# CNC-InterfaceBoard.net
KiCad netlist of a schematic drawn in EAGLE
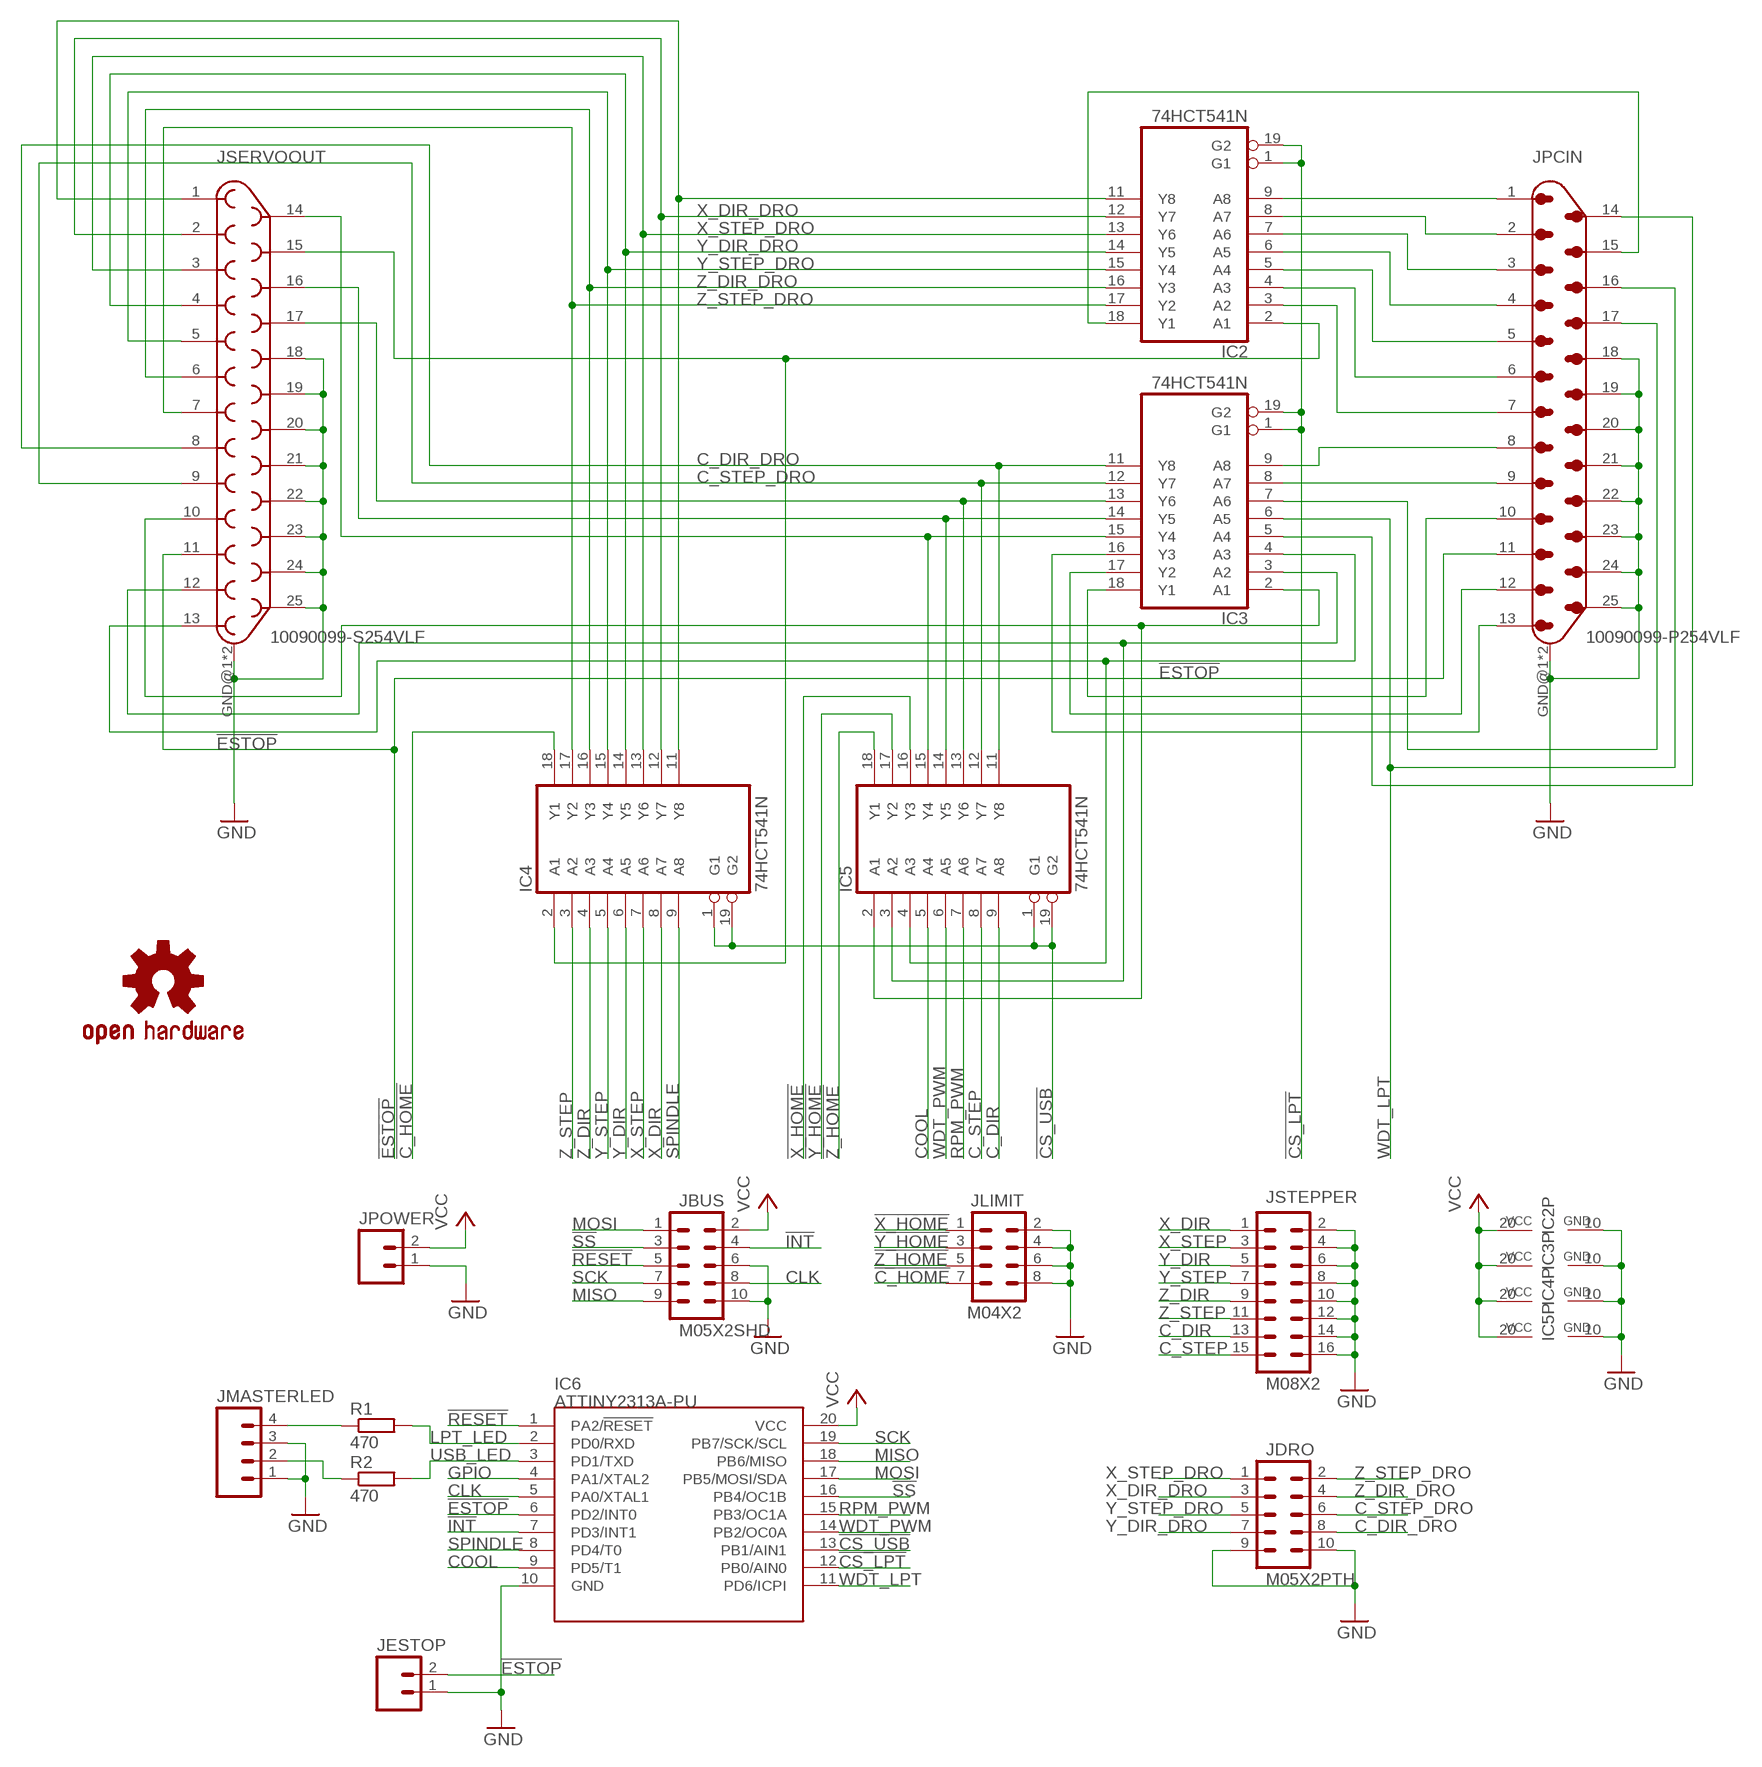
[diagram p0: schematic, sheet 1]

(export (version "E")
  (design (tool "Eeschema 10.0.6"))
  (components
    (comp (ref "IC2")
      (value "74HCT541N")
      (footprint "eagle-import:DIL20")
      (libsource (lib "eagle-import") (part "74541NHCT"))
    )
    (comp (ref "IC3")
      (value "74HCT541N")
      (footprint "eagle-import:DIL20")
      (libsource (lib "eagle-import") (part "74541NHCT"))
    )
    (comp (ref "IC4")
      (value "74HCT541N")
      (footprint "eagle-import:DIL20")
      (libsource (lib "eagle-import") (part "74541NHCT"))
    )
    (comp (ref "IC5")
      (value "74HCT541N")
      (footprint "eagle-import:DIL20")
      (libsource (lib "eagle-import") (part "74541NHCT"))
    )
    (comp (ref "IC6")
      (value "ATTINY2313A-PU")
      (footprint "eagle-import:DIP254P762X533-20")
      (libsource (lib "eagle-import") (part "ATTINY2313A-PU"))
    )
    (comp (ref "JBUS")
      (value "M05X2SHD")
      (footprint "eagle-import:2X5-SHROUDED")
      (libsource (lib "eagle-import") (part "M05X2SHD"))
    )
    (comp (ref "JDRO")
      (value "M05X2PTH")
      (footprint "eagle-import:AVR_ICSP")
      (libsource (lib "eagle-import") (part "M05X2PTH"))
    )
    (comp (ref "JESTOP")
      (value "M02PTH")
      (footprint "eagle-import:1X02")
      (libsource (lib "eagle-import") (part "M02PTH"))
    )
    (comp (ref "JLIMIT")
      (value "M04X2")
      (footprint "eagle-import:2X4")
      (libsource (lib "eagle-import") (part "M04X2"))
    )
    (comp (ref "JMASTERLED")
      (value "M04PTH")
      (footprint "eagle-import:1X04")
      (libsource (lib "eagle-import") (part "M04PTH"))
    )
    (comp (ref "JPCIN")
      (value "10090099-P254VLF")
      (footprint "eagle-import:10090099-P254VLF")
      (libsource (lib "eagle-import") (part "10090099-P254VLF"))
    )
    (comp (ref "JPOWER")
      (value "M02POLAR")
      (footprint "eagle-import:MOLEX-1X2")
      (libsource (lib "eagle-import") (part "M02POLAR"))
    )
    (comp (ref "JSERVOOUT")
      (value "10090099-S254VLF")
      (footprint "eagle-import:10090099-S254VLF")
      (libsource (lib "eagle-import") (part "10090099-S254VLF"))
    )
    (comp (ref "JSTEPPER")
      (value "M08X2")
      (footprint "eagle-import:2X8")
      (libsource (lib "eagle-import") (part "M08X2"))
    )
    (comp (ref "R1")
      (value "470")
      (footprint "eagle-import:0207_10")
      (libsource (lib "eagle-import") (part "R-EU_0207/10"))
    )
    (comp (ref "R2")
      (value "470")
      (footprint "eagle-import:0207_10")
      (libsource (lib "eagle-import") (part "R-EU_0207/10"))
    )
    (comp (ref "U$1")
      (value "SPARKFUN_OSHW-LOGOL")
      (footprint "eagle-import:SPARKFUN_OSHW-LOGO-L")
      (libsource (lib "eagle-import") (part "SPARKFUN_OSHW-LOGOL"))
    )
  )
  (nets
    (net (code "1") (name "/CLK") (class "Default")
      (node (ref "IC6") (pin "5") (pinfunction "PA0/XTAL1_5") (pintype "bidirectional"))
      (node (ref "JBUS") (pin "8") (pinfunction "8_8") (pintype "passive"))
    )
    (net (code "2") (name "/COOL") (class "Default")
      (node (ref "IC5") (pin "5") (pinfunction "A4_5") (pintype "input"))
      (node (ref "IC6") (pin "9") (pinfunction "PD5/T1_9") (pintype "bidirectional"))
    )
    (net (code "3") (name "/C_DIR") (class "Default")
      (node (ref "IC5") (pin "9") (pinfunction "A8_9") (pintype "input"))
      (node (ref "JSTEPPER") (pin "13") (pinfunction "13_13") (pintype "passive"))
    )
    (net (code "4") (name "/C_DIR_DRO") (class "Default")
      (node (ref "IC3") (pin "11") (pinfunction "Y8_11") (pintype "tri_state"))
      (node (ref "IC5") (pin "11") (pinfunction "Y8_11") (pintype "tri_state"))
      (node (ref "JDRO") (pin "8") (pinfunction "8_8") (pintype "passive"))
      (node (ref "JSERVOOUT") (pin "8") (pinfunction "8_8") (pintype "passive"))
    )
    (net (code "5") (name "/C_STEP") (class "Default")
      (node (ref "IC5") (pin "8") (pinfunction "A7_8") (pintype "input"))
      (node (ref "JSTEPPER") (pin "15") (pinfunction "15_15") (pintype "passive"))
    )
    (net (code "6") (name "/C_STEP_DRO") (class "Default")
      (node (ref "IC3") (pin "12") (pinfunction "Y7_12") (pintype "tri_state"))
      (node (ref "IC5") (pin "12") (pinfunction "Y7_12") (pintype "tri_state"))
      (node (ref "JDRO") (pin "6") (pinfunction "6_6") (pintype "passive"))
      (node (ref "JSERVOOUT") (pin "9") (pinfunction "9_9") (pintype "passive"))
    )
    (net (code "7") (name "/GPIO") (class "Default")
      (node (ref "IC6") (pin "4") (pinfunction "PA1/XTAL2_4") (pintype "bidirectional"))
    )
    (net (code "8") (name "/LPT_LED") (class "Default")
      (node (ref "IC6") (pin "2") (pinfunction "PD0/RXD_2") (pintype "bidirectional"))
      (node (ref "R1") (pin "2") (pinfunction "2_2") (pintype "passive"))
    )
    (net (code "9") (name "/MISO") (class "Default")
      (node (ref "IC6") (pin "18") (pinfunction "PB6/MISO_18") (pintype "bidirectional"))
      (node (ref "JBUS") (pin "9") (pinfunction "9_9") (pintype "passive"))
    )
    (net (code "10") (name "/MOSI") (class "Default")
      (node (ref "IC6") (pin "17") (pinfunction "PB5/MOSI/SDA_17") (pintype "bidirectional"))
      (node (ref "JBUS") (pin "1") (pinfunction "1_1") (pintype "passive"))
    )
    (net (code "11") (name "/RPM_PWM") (class "Default")
      (node (ref "IC5") (pin "7") (pinfunction "A6_7") (pintype "input"))
      (node (ref "IC6") (pin "15") (pinfunction "PB3/OC1A_15") (pintype "bidirectional"))
    )
    (net (code "12") (name "/SCK") (class "Default")
      (node (ref "IC6") (pin "19") (pinfunction "PB7/SCK/SCL_19") (pintype "bidirectional"))
      (node (ref "JBUS") (pin "7") (pinfunction "7_7") (pintype "passive"))
    )
    (net (code "13") (name "/SPINDLE") (class "Default")
      (node (ref "IC4") (pin "9") (pinfunction "A8_9") (pintype "input"))
      (node (ref "IC6") (pin "8") (pinfunction "PD4/T0_8") (pintype "bidirectional"))
    )
    (net (code "14") (name "/USB_LED") (class "Default")
      (node (ref "IC6") (pin "3") (pinfunction "PD1/TXD_3") (pintype "bidirectional"))
      (node (ref "R2") (pin "2") (pinfunction "2_2") (pintype "passive"))
    )
    (net (code "15") (name "/WDT_LPT") (class "Default")
      (node (ref "IC3") (pin "6") (pinfunction "A5_6") (pintype "input"))
      (node (ref "IC6") (pin "11") (pinfunction "PD6/ICPI_11") (pintype "bidirectional"))
      (node (ref "JPCIN") (pin "16") (pinfunction "16_16") (pintype "passive"))
    )
    (net (code "16") (name "/WDT_PWM") (class "Default")
      (node (ref "IC5") (pin "6") (pinfunction "A5_6") (pintype "input"))
      (node (ref "IC6") (pin "14") (pinfunction "PB2/OC0A_14") (pintype "bidirectional"))
    )
    (net (code "17") (name "/X_DIR") (class "Default")
      (node (ref "IC4") (pin "8") (pinfunction "A7_8") (pintype "input"))
      (node (ref "JSTEPPER") (pin "1") (pinfunction "1_1") (pintype "passive"))
    )
    (net (code "18") (name "/X_DIR_DRO") (class "Default")
      (node (ref "IC2") (pin "12") (pinfunction "Y7_12") (pintype "tri_state"))
      (node (ref "IC4") (pin "12") (pinfunction "Y7_12") (pintype "tri_state"))
      (node (ref "JDRO") (pin "3") (pinfunction "3_3") (pintype "passive"))
      (node (ref "JSERVOOUT") (pin "2") (pinfunction "2_2") (pintype "passive"))
    )
    (net (code "19") (name "/X_STEP") (class "Default")
      (node (ref "IC4") (pin "7") (pinfunction "A6_7") (pintype "input"))
      (node (ref "JSTEPPER") (pin "3") (pinfunction "3_3") (pintype "passive"))
    )
    (net (code "20") (name "/X_STEP_DRO") (class "Default")
      (node (ref "IC2") (pin "13") (pinfunction "Y6_13") (pintype "tri_state"))
      (node (ref "IC4") (pin "13") (pinfunction "Y6_13") (pintype "tri_state"))
      (node (ref "JDRO") (pin "1") (pinfunction "1_1") (pintype "passive"))
      (node (ref "JSERVOOUT") (pin "3") (pinfunction "3_3") (pintype "passive"))
    )
    (net (code "21") (name "/Y_DIR") (class "Default")
      (node (ref "IC4") (pin "6") (pinfunction "A5_6") (pintype "input"))
      (node (ref "JSTEPPER") (pin "5") (pinfunction "5_5") (pintype "passive"))
    )
    (net (code "22") (name "/Y_DIR_DRO") (class "Default")
      (node (ref "IC2") (pin "14") (pinfunction "Y5_14") (pintype "tri_state"))
      (node (ref "IC4") (pin "14") (pinfunction "Y5_14") (pintype "tri_state"))
      (node (ref "JDRO") (pin "7") (pinfunction "7_7") (pintype "passive"))
      (node (ref "JSERVOOUT") (pin "4") (pinfunction "4_4") (pintype "passive"))
    )
    (net (code "23") (name "/Y_STEP") (class "Default")
      (node (ref "IC4") (pin "5") (pinfunction "A4_5") (pintype "input"))
      (node (ref "JSTEPPER") (pin "7") (pinfunction "7_7") (pintype "passive"))
    )
    (net (code "24") (name "/Y_STEP_DRO") (class "Default")
      (node (ref "IC2") (pin "15") (pinfunction "Y4_15") (pintype "tri_state"))
      (node (ref "IC4") (pin "15") (pinfunction "Y4_15") (pintype "tri_state"))
      (node (ref "JDRO") (pin "5") (pinfunction "5_5") (pintype "passive"))
      (node (ref "JSERVOOUT") (pin "5") (pinfunction "5_5") (pintype "passive"))
    )
    (net (code "25") (name "/Z_DIR") (class "Default")
      (node (ref "IC4") (pin "4") (pinfunction "A3_4") (pintype "input"))
      (node (ref "JSTEPPER") (pin "9") (pinfunction "9_9") (pintype "passive"))
    )
    (net (code "26") (name "/Z_DIR_DRO") (class "Default")
      (node (ref "IC2") (pin "16") (pinfunction "Y3_16") (pintype "tri_state"))
      (node (ref "IC4") (pin "16") (pinfunction "Y3_16") (pintype "tri_state"))
      (node (ref "JDRO") (pin "4") (pinfunction "4_4") (pintype "passive"))
      (node (ref "JSERVOOUT") (pin "6") (pinfunction "6_6") (pintype "passive"))
    )
    (net (code "27") (name "/Z_STEP") (class "Default")
      (node (ref "IC4") (pin "3") (pinfunction "A2_3") (pintype "input"))
      (node (ref "JSTEPPER") (pin "11") (pinfunction "11_11") (pintype "passive"))
    )
    (net (code "28") (name "/Z_STEP_DRO") (class "Default")
      (node (ref "IC2") (pin "17") (pinfunction "Y2_17") (pintype "tri_state"))
      (node (ref "IC4") (pin "17") (pinfunction "Y2_17") (pintype "tri_state"))
      (node (ref "JDRO") (pin "2") (pinfunction "2_2") (pintype "passive"))
      (node (ref "JSERVOOUT") (pin "7") (pinfunction "7_7") (pintype "passive"))
    )
    (net (code "29") (name "/~{CS_LPT}") (class "Default")
      (node (ref "IC2") (pin "1") (pinfunction "G1_1") (pintype "input"))
      (node (ref "IC2") (pin "19") (pinfunction "G2_19") (pintype "input"))
      (node (ref "IC3") (pin "1") (pinfunction "G1_1") (pintype "input"))
      (node (ref "IC3") (pin "19") (pinfunction "G2_19") (pintype "input"))
      (node (ref "IC6") (pin "12") (pinfunction "PB0/AIN0_12") (pintype "bidirectional"))
    )
    (net (code "30") (name "/~{CS_USB}") (class "Default")
      (node (ref "IC4") (pin "1") (pinfunction "G1_1") (pintype "input"))
      (node (ref "IC4") (pin "19") (pinfunction "G2_19") (pintype "input"))
      (node (ref "IC5") (pin "1") (pinfunction "G1_1") (pintype "input"))
      (node (ref "IC5") (pin "19") (pinfunction "G2_19") (pintype "input"))
      (node (ref "IC6") (pin "13") (pinfunction "PB1/AIN1_13") (pintype "bidirectional"))
    )
    (net (code "31") (name "/~{C_HOME}") (class "Default")
      (node (ref "IC4") (pin "18") (pinfunction "Y1_18") (pintype "tri_state"))
      (node (ref "JLIMIT") (pin "7") (pinfunction "7_7") (pintype "passive"))
    )
    (net (code "32") (name "/~{ESTOP}") (class "Default")
      (node (ref "IC6") (pin "6") (pinfunction "PD2/INT0_6") (pintype "bidirectional"))
      (node (ref "JESTOP") (pin "2") (pinfunction "2_2") (pintype "passive"))
      (node (ref "JPCIN") (pin "11") (pinfunction "11_11") (pintype "passive"))
      (node (ref "JSERVOOUT") (pin "11") (pinfunction "11_11") (pintype "passive"))
    )
    (net (code "33") (name "/~{INT}") (class "Default")
      (node (ref "IC6") (pin "7") (pinfunction "PD3/INT1_7") (pintype "bidirectional"))
      (node (ref "JBUS") (pin "4") (pinfunction "4_4") (pintype "passive"))
    )
    (net (code "34") (name "/~{RESET}") (class "Default")
      (node (ref "IC6") (pin "1") (pinfunction "PA2/~{RESET}_1") (pintype "bidirectional"))
      (node (ref "JBUS") (pin "5") (pinfunction "5_5") (pintype "passive"))
    )
    (net (code "35") (name "/~{SS}") (class "Default")
      (node (ref "IC6") (pin "16") (pinfunction "PB4/OC1B_16") (pintype "bidirectional"))
      (node (ref "JBUS") (pin "3") (pinfunction "3_3") (pintype "passive"))
    )
    (net (code "36") (name "/~{X_HOME}") (class "Default")
      (node (ref "IC5") (pin "16") (pinfunction "Y3_16") (pintype "tri_state"))
      (node (ref "JLIMIT") (pin "1") (pinfunction "1_1") (pintype "passive"))
    )
    (net (code "37") (name "/~{Y_HOME}") (class "Default")
      (node (ref "IC5") (pin "17") (pinfunction "Y2_17") (pintype "tri_state"))
      (node (ref "JLIMIT") (pin "3") (pinfunction "3_3") (pintype "passive"))
    )
    (net (code "38") (name "/~{Z_HOME}") (class "Default")
      (node (ref "IC5") (pin "18") (pinfunction "Y1_18") (pintype "tri_state"))
      (node (ref "JLIMIT") (pin "5") (pinfunction "5_5") (pintype "passive"))
    )
    (net (code "39") (name "GND") (class "Default")
      (node (ref "IC2") (pin "10") (pinfunction "GND_10") (pintype "power_in"))
      (node (ref "IC3") (pin "10") (pinfunction "GND_10") (pintype "power_in"))
      (node (ref "IC4") (pin "10") (pinfunction "GND_10") (pintype "power_in"))
      (node (ref "IC5") (pin "10") (pinfunction "GND_10") (pintype "power_in"))
      (node (ref "IC6") (pin "10") (pinfunction "GND_10") (pintype "bidirectional"))
      (node (ref "JBUS") (pin "10") (pinfunction "10_10") (pintype "passive"))
      (node (ref "JBUS") (pin "6") (pinfunction "6_6") (pintype "passive"))
      (node (ref "JDRO") (pin "10") (pinfunction "10_10") (pintype "passive"))
      (node (ref "JDRO") (pin "9") (pinfunction "9_9") (pintype "passive"))
      (node (ref "JESTOP") (pin "1") (pinfunction "1_1") (pintype "passive"))
      (node (ref "JLIMIT") (pin "2") (pinfunction "2_2") (pintype "passive"))
      (node (ref "JLIMIT") (pin "4") (pinfunction "4_4") (pintype "passive"))
      (node (ref "JLIMIT") (pin "6") (pinfunction "6_6") (pintype "passive"))
      (node (ref "JLIMIT") (pin "8") (pinfunction "8_8") (pintype "passive"))
      (node (ref "JMASTERLED") (pin "1") (pinfunction "1_1") (pintype "passive"))
      (node (ref "JMASTERLED") (pin "3") (pinfunction "3_3") (pintype "passive"))
      (node (ref "JPCIN") (pin "18") (pinfunction "18_18") (pintype "passive"))
      (node (ref "JPCIN") (pin "19") (pinfunction "19_19") (pintype "passive"))
      (node (ref "JPCIN") (pin "20") (pinfunction "20_20") (pintype "passive"))
      (node (ref "JPCIN") (pin "21") (pinfunction "21_21") (pintype "passive"))
      (node (ref "JPCIN") (pin "22") (pinfunction "22_22") (pintype "passive"))
      (node (ref "JPCIN") (pin "23") (pinfunction "23_23") (pintype "passive"))
      (node (ref "JPCIN") (pin "24") (pinfunction "24_24") (pintype "passive"))
      (node (ref "JPCIN") (pin "25") (pinfunction "25_25") (pintype "passive"))
      (node (ref "JPCIN") (pin "GND@1") (pinfunction "GND_GND@1") (pintype "power_in"))
      (node (ref "JPCIN") (pin "GND@2") (pinfunction "GND_GND@2") (pintype "power_in"))
      (node (ref "JPOWER") (pin "1") (pinfunction "1_1") (pintype "passive"))
      (node (ref "JSERVOOUT") (pin "18") (pinfunction "18_18") (pintype "passive"))
      (node (ref "JSERVOOUT") (pin "19") (pinfunction "19_19") (pintype "passive"))
      (node (ref "JSERVOOUT") (pin "20") (pinfunction "20_20") (pintype "passive"))
      (node (ref "JSERVOOUT") (pin "21") (pinfunction "21_21") (pintype "passive"))
      (node (ref "JSERVOOUT") (pin "22") (pinfunction "22_22") (pintype "passive"))
      (node (ref "JSERVOOUT") (pin "23") (pinfunction "23_23") (pintype "passive"))
      (node (ref "JSERVOOUT") (pin "24") (pinfunction "24_24") (pintype "passive"))
      (node (ref "JSERVOOUT") (pin "25") (pinfunction "25_25") (pintype "passive"))
      (node (ref "JSERVOOUT") (pin "GND@1") (pinfunction "GND_GND@1") (pintype "power_in"))
      (node (ref "JSERVOOUT") (pin "GND@2") (pinfunction "GND_GND@2") (pintype "power_in"))
      (node (ref "JSTEPPER") (pin "10") (pinfunction "10_10") (pintype "passive"))
      (node (ref "JSTEPPER") (pin "12") (pinfunction "12_12") (pintype "passive"))
      (node (ref "JSTEPPER") (pin "14") (pinfunction "14_14") (pintype "passive"))
      (node (ref "JSTEPPER") (pin "16") (pinfunction "16_16") (pintype "passive"))
      (node (ref "JSTEPPER") (pin "2") (pinfunction "2_2") (pintype "passive"))
      (node (ref "JSTEPPER") (pin "4") (pinfunction "4_4") (pintype "passive"))
      (node (ref "JSTEPPER") (pin "6") (pinfunction "6_6") (pintype "passive"))
      (node (ref "JSTEPPER") (pin "8") (pinfunction "8_8") (pintype "passive"))
    )
    (net (code "40") (name "Net-(IC2A-A1)") (class "Default")
      (node (ref "IC2") (pin "2") (pinfunction "A1_2") (pintype "input"))
      (node (ref "IC4") (pin "2") (pinfunction "A1_2") (pintype "input"))
      (node (ref "JSERVOOUT") (pin "15") (pinfunction "15_15") (pintype "passive"))
    )
    (net (code "41") (name "Net-(IC2A-A2)") (class "Default")
      (node (ref "IC2") (pin "3") (pinfunction "A2_3") (pintype "input"))
      (node (ref "JPCIN") (pin "7") (pinfunction "7_7") (pintype "passive"))
    )
    (net (code "42") (name "Net-(IC2A-A3)") (class "Default")
      (node (ref "IC2") (pin "4") (pinfunction "A3_4") (pintype "input"))
      (node (ref "JPCIN") (pin "6") (pinfunction "6_6") (pintype "passive"))
    )
    (net (code "43") (name "Net-(IC2A-A4)") (class "Default")
      (node (ref "IC2") (pin "5") (pinfunction "A4_5") (pintype "input"))
      (node (ref "JPCIN") (pin "5") (pinfunction "5_5") (pintype "passive"))
    )
    (net (code "44") (name "Net-(IC2A-A5)") (class "Default")
      (node (ref "IC2") (pin "6") (pinfunction "A5_6") (pintype "input"))
      (node (ref "JPCIN") (pin "4") (pinfunction "4_4") (pintype "passive"))
    )
    (net (code "45") (name "Net-(IC2A-A6)") (class "Default")
      (node (ref "IC2") (pin "7") (pinfunction "A6_7") (pintype "input"))
      (node (ref "JPCIN") (pin "3") (pinfunction "3_3") (pintype "passive"))
    )
    (net (code "46") (name "Net-(IC2A-A7)") (class "Default")
      (node (ref "IC2") (pin "8") (pinfunction "A7_8") (pintype "input"))
      (node (ref "JPCIN") (pin "2") (pinfunction "2_2") (pintype "passive"))
    )
    (net (code "47") (name "Net-(IC2A-A8)") (class "Default")
      (node (ref "IC2") (pin "9") (pinfunction "A8_9") (pintype "input"))
      (node (ref "JPCIN") (pin "1") (pinfunction "1_1") (pintype "passive"))
    )
    (net (code "48") (name "Net-(IC2A-Y1)") (class "Default")
      (node (ref "IC2") (pin "18") (pinfunction "Y1_18") (pintype "tri_state"))
      (node (ref "JPCIN") (pin "15") (pinfunction "15_15") (pintype "passive"))
    )
    (net (code "49") (name "Net-(IC2A-Y8)") (class "Default")
      (node (ref "IC2") (pin "11") (pinfunction "Y8_11") (pintype "tri_state"))
      (node (ref "IC4") (pin "11") (pinfunction "Y8_11") (pintype "tri_state"))
      (node (ref "JSERVOOUT") (pin "1") (pinfunction "1_1") (pintype "passive"))
    )
    (net (code "50") (name "Net-(IC3A-A1)") (class "Default")
      (node (ref "IC3") (pin "2") (pinfunction "A1_2") (pintype "input"))
      (node (ref "IC5") (pin "2") (pinfunction "A1_2") (pintype "input"))
      (node (ref "JSERVOOUT") (pin "10") (pinfunction "10_10") (pintype "passive"))
    )
    (net (code "51") (name "Net-(IC3A-A2)") (class "Default")
      (node (ref "IC3") (pin "3") (pinfunction "A2_3") (pintype "input"))
      (node (ref "IC5") (pin "3") (pinfunction "A2_3") (pintype "input"))
      (node (ref "JSERVOOUT") (pin "12") (pinfunction "12_12") (pintype "passive"))
    )
    (net (code "52") (name "Net-(IC3A-A3)") (class "Default")
      (node (ref "IC3") (pin "4") (pinfunction "A3_4") (pintype "input"))
      (node (ref "IC5") (pin "4") (pinfunction "A3_4") (pintype "input"))
      (node (ref "JSERVOOUT") (pin "13") (pinfunction "13_13") (pintype "passive"))
    )
    (net (code "53") (name "Net-(IC3A-A4)") (class "Default")
      (node (ref "IC3") (pin "5") (pinfunction "A4_5") (pintype "input"))
      (node (ref "JPCIN") (pin "14") (pinfunction "14_14") (pintype "passive"))
    )
    (net (code "54") (name "Net-(IC3A-A6)") (class "Default")
      (node (ref "IC3") (pin "7") (pinfunction "A6_7") (pintype "input"))
      (node (ref "JPCIN") (pin "17") (pinfunction "17_17") (pintype "passive"))
    )
    (net (code "55") (name "Net-(IC3A-A7)") (class "Default")
      (node (ref "IC3") (pin "8") (pinfunction "A7_8") (pintype "input"))
      (node (ref "JPCIN") (pin "9") (pinfunction "9_9") (pintype "passive"))
    )
    (net (code "56") (name "Net-(IC3A-A8)") (class "Default")
      (node (ref "IC3") (pin "9") (pinfunction "A8_9") (pintype "input"))
      (node (ref "JPCIN") (pin "8") (pinfunction "8_8") (pintype "passive"))
    )
    (net (code "57") (name "Net-(IC3A-Y1)") (class "Default")
      (node (ref "IC3") (pin "18") (pinfunction "Y1_18") (pintype "tri_state"))
      (node (ref "JPCIN") (pin "10") (pinfunction "10_10") (pintype "passive"))
    )
    (net (code "58") (name "Net-(IC3A-Y2)") (class "Default")
      (node (ref "IC3") (pin "17") (pinfunction "Y2_17") (pintype "tri_state"))
      (node (ref "JPCIN") (pin "12") (pinfunction "12_12") (pintype "passive"))
    )
    (net (code "59") (name "Net-(IC3A-Y3)") (class "Default")
      (node (ref "IC3") (pin "16") (pinfunction "Y3_16") (pintype "tri_state"))
      (node (ref "JPCIN") (pin "13") (pinfunction "13_13") (pintype "passive"))
    )
    (net (code "60") (name "Net-(IC3A-Y4)") (class "Default")
      (node (ref "IC3") (pin "15") (pinfunction "Y4_15") (pintype "tri_state"))
      (node (ref "IC5") (pin "15") (pinfunction "Y4_15") (pintype "tri_state"))
      (node (ref "JSERVOOUT") (pin "14") (pinfunction "14_14") (pintype "passive"))
    )
    (net (code "61") (name "Net-(IC3A-Y5)") (class "Default")
      (node (ref "IC3") (pin "14") (pinfunction "Y5_14") (pintype "tri_state"))
      (node (ref "IC5") (pin "14") (pinfunction "Y5_14") (pintype "tri_state"))
      (node (ref "JSERVOOUT") (pin "16") (pinfunction "16_16") (pintype "passive"))
    )
    (net (code "62") (name "Net-(IC3A-Y6)") (class "Default")
      (node (ref "IC3") (pin "13") (pinfunction "Y6_13") (pintype "tri_state"))
      (node (ref "IC5") (pin "13") (pinfunction "Y6_13") (pintype "tri_state"))
      (node (ref "JSERVOOUT") (pin "17") (pinfunction "17_17") (pintype "passive"))
    )
    (net (code "63") (name "Net-(JMASTERLED-Pad2)") (class "Default")
      (node (ref "JMASTERLED") (pin "2") (pinfunction "2_2") (pintype "passive"))
      (node (ref "R2") (pin "1") (pinfunction "1_1") (pintype "passive"))
    )
    (net (code "64") (name "Net-(JMASTERLED-Pad4)") (class "Default")
      (node (ref "JMASTERLED") (pin "4") (pinfunction "4_4") (pintype "passive"))
      (node (ref "R1") (pin "1") (pinfunction "1_1") (pintype "passive"))
    )
    (net (code "65") (name "VCC") (class "Default")
      (node (ref "IC2") (pin "20") (pinfunction "VCC_20") (pintype "power_in"))
      (node (ref "IC3") (pin "20") (pinfunction "VCC_20") (pintype "power_in"))
      (node (ref "IC4") (pin "20") (pinfunction "VCC_20") (pintype "power_in"))
      (node (ref "IC5") (pin "20") (pinfunction "VCC_20") (pintype "power_in"))
      (node (ref "IC6") (pin "20") (pinfunction "VCC_20") (pintype "bidirectional"))
      (node (ref "JBUS") (pin "2") (pinfunction "2_2") (pintype "passive"))
      (node (ref "JPOWER") (pin "2") (pinfunction "2_2") (pintype "passive"))
    )
  )
)
